# CHIP_dispv2_0.net
KiCad netlist of a schematic drawn in EAGLE
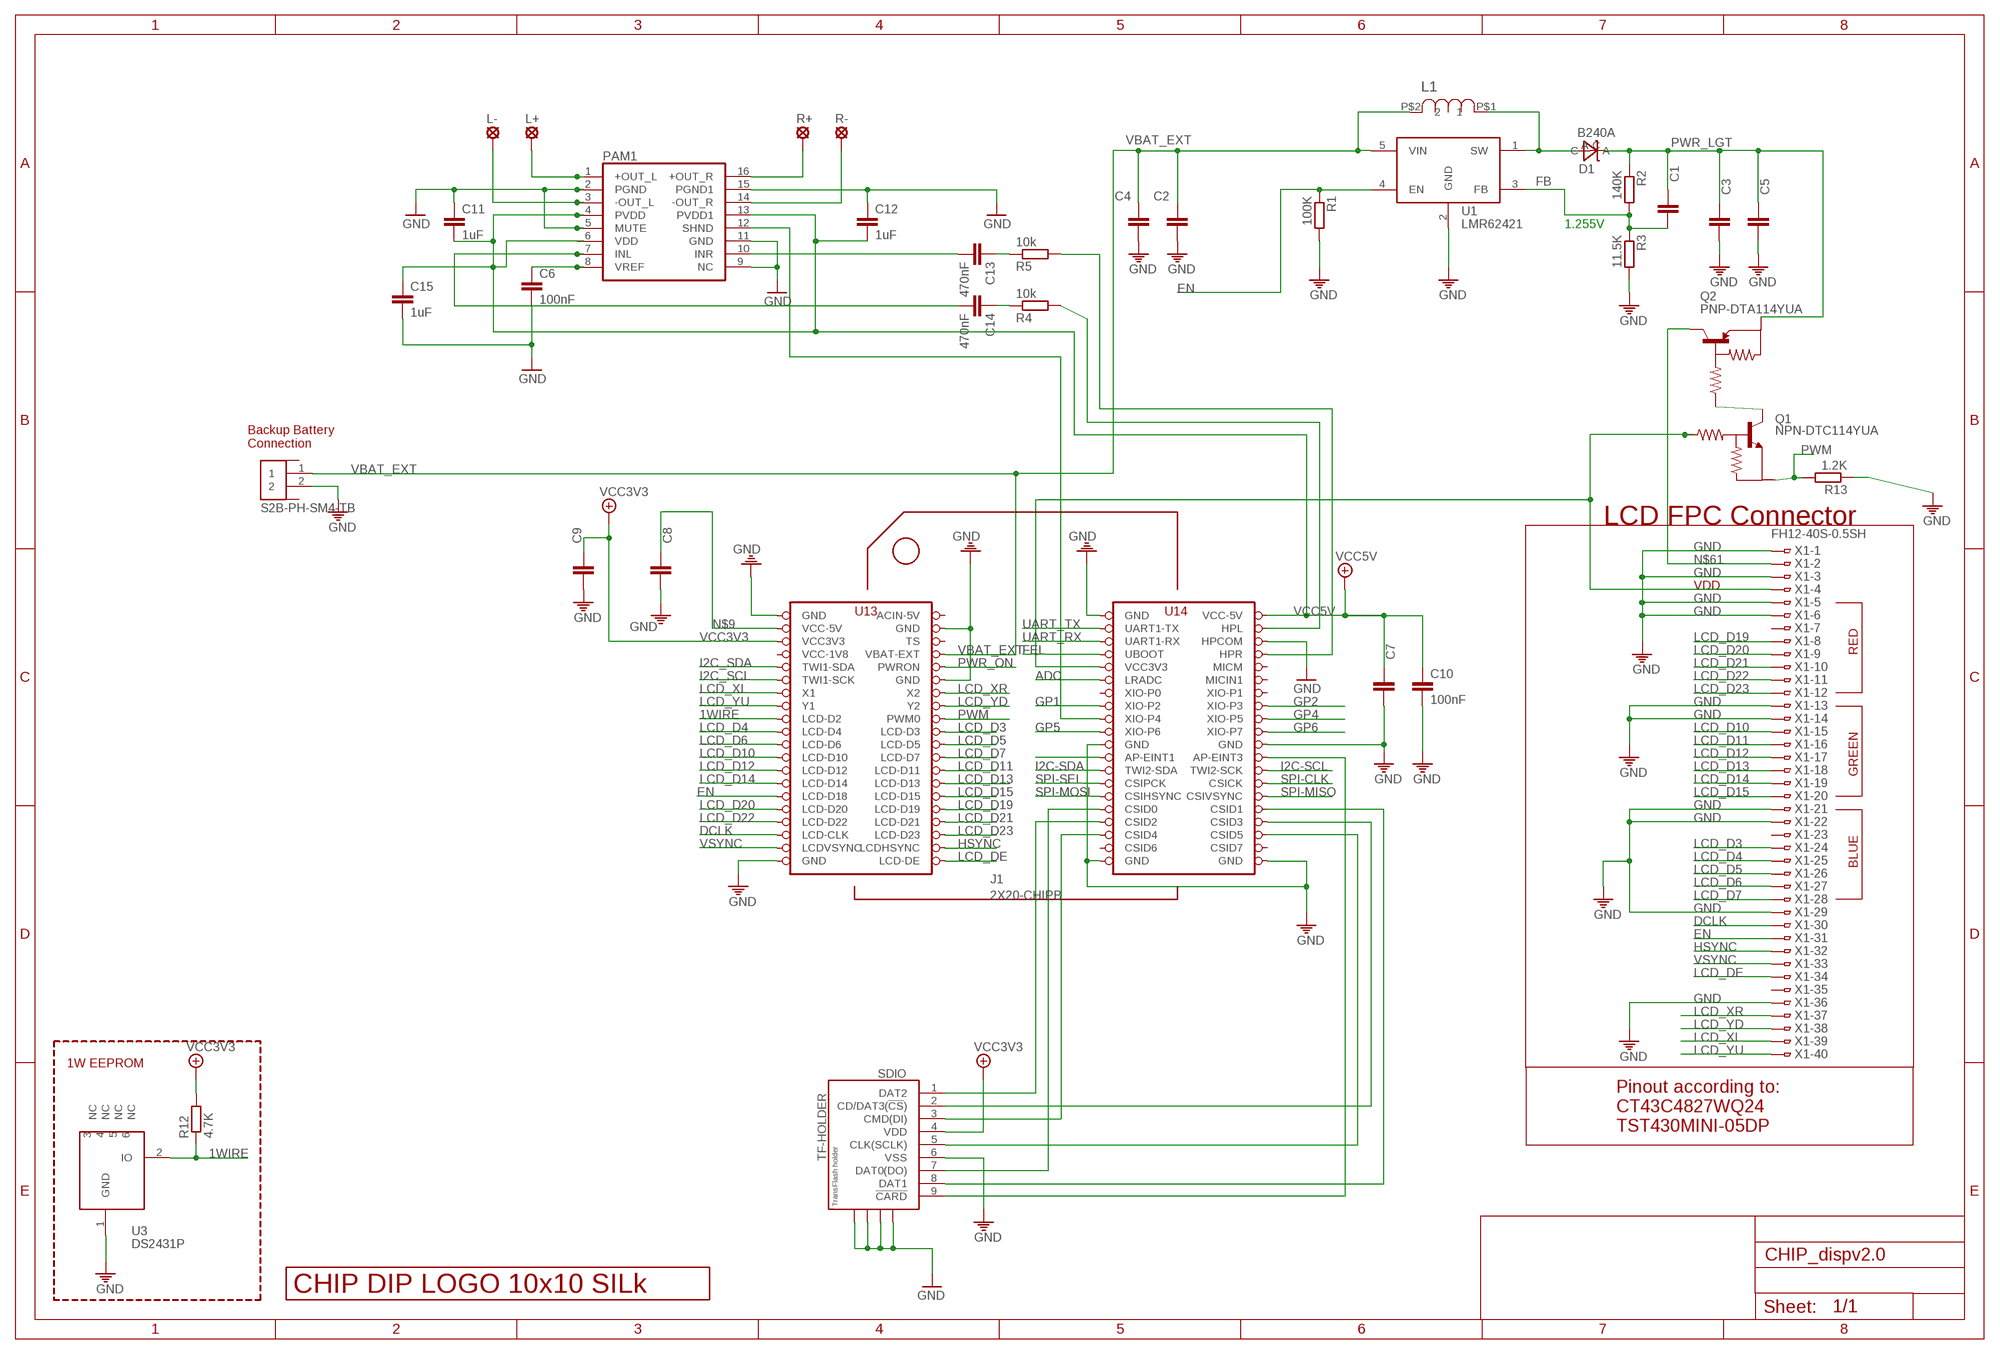
[diagram p0: schematic, sheet 1]

(export (version "E")
  (design (tool "Eeschema 10.0.6"))
  (components
    (comp (ref "C1")
      (value "220pF")
      (footprint "eagle-import:C0805")
      (libsource (lib "eagle-import") (part "C-EUC0805"))
    )
    (comp (ref "C2")
      (value "100nF")
      (footprint "eagle-import:C0805")
      (libsource (lib "eagle-import") (part "C-EUC0805"))
    )
    (comp (ref "C3")
      (value "100nF")
      (footprint "eagle-import:C0805")
      (libsource (lib "eagle-import") (part "C-EUC0805"))
    )
    (comp (ref "C4")
      (value "22uF")
      (footprint "eagle-import:C0805")
      (libsource (lib "eagle-import") (part "C-EUC0805"))
    )
    (comp (ref "C5")
      (value "22uF")
      (footprint "eagle-import:C0805")
      (libsource (lib "eagle-import") (part "C-EUC0805"))
    )
    (comp (ref "C6")
      (value "100nF")
      (footprint "eagle-import:C0805")
      (libsource (lib "eagle-import") (part "C-EUC0805"))
    )
    (comp (ref "C7")
      (value "22uF")
      (footprint "eagle-import:C0805")
      (libsource (lib "eagle-import") (part "C-EUC0805"))
    )
    (comp (ref "C8")
      (value "100nF")
      (footprint "eagle-import:C0805")
      (libsource (lib "eagle-import") (part "C-EUC0805"))
    )
    (comp (ref "C9")
      (value "100nF")
      (footprint "eagle-import:C0805")
      (libsource (lib "eagle-import") (part "C-EUC0805"))
    )
    (comp (ref "C10")
      (value "100nF")
      (footprint "eagle-import:C0805")
      (libsource (lib "eagle-import") (part "C-EUC0805"))
    )
    (comp (ref "C11")
      (value "1uF")
      (footprint "eagle-import:C0805")
      (libsource (lib "eagle-import") (part "C-EUC0805"))
    )
    (comp (ref "C12")
      (value "1uF")
      (footprint "eagle-import:C0805")
      (libsource (lib "eagle-import") (part "C-EUC0805"))
    )
    (comp (ref "C13")
      (value "470nF")
      (footprint "eagle-import:C0805")
      (libsource (lib "eagle-import") (part "C-EUC0805"))
    )
    (comp (ref "C14")
      (value "470nF")
      (footprint "eagle-import:C0805")
      (libsource (lib "eagle-import") (part "C-EUC0805"))
    )
    (comp (ref "C15")
      (value "1uF")
      (footprint "eagle-import:C0805")
      (libsource (lib "eagle-import") (part "C-EUC0805"))
    )
    (comp (ref "D1")
      (value "B240A")
      (footprint "eagle-import:DO-214AC")
      (fields (field (name "MFG") "DIGIKEY") (field (name "VENDOR_PART_NUMBER") "B240A-13-F"))
      (libsource (lib "eagle-import") (part "DIODE_SCHTKY_B240"))
    )
    (comp (ref "J1")
      (value "2X20-CHIPB")
      (footprint "eagle-import:2X20CHIP_SM")
      (libsource (lib "eagle-import") (part "2X20-CHIPB"))
    )
    (comp (ref "J3")
      (value "S2B-PH-SM4-TB")
      (footprint "eagle-import:S2B-PH-SM4-TB")
      (fields (field (name "MFG") "DIGIKEY") (field (name "VENDOR_PART_NUMBER") "S2B-PH-SM4-TB(LF)(SN)"))
      (libsource (lib "eagle-import") (part "S2B-PH-SM4-TB"))
    )
    (comp (ref "L+")
      (value "SE11")
      (footprint "eagle-import:SE11")
      (libsource (lib "eagle-import") (part "SE11"))
    )
    (comp (ref "L-")
      (value "SE11")
      (footprint "eagle-import:SE11")
      (libsource (lib "eagle-import") (part "SE11"))
    )
    (comp (ref "L1")
      (value "SRN6045-100M")
      (footprint "eagle-import:SRN6045")
      (fields (field (name "MFG") "DIGIKEY"))
      (libsource (lib "eagle-import") (part "SRN6045-100M"))
    )
    (comp (ref "PAM1")
      (value "PAM8403")
      (footprint "eagle-import:SOP-16")
      (libsource (lib "eagle-import") (part "PAM8403"))
    )
    (comp (ref "Q1")
      (value "NPN-DTC114YUA")
      (footprint "eagle-import:SOT323")
      (libsource (lib "eagle-import") (part "NPN-DTC114YUA"))
    )
    (comp (ref "Q2")
      (value "PNP-DTA114YUA")
      (footprint "eagle-import:SOT323")
      (libsource (lib "eagle-import") (part "PNP-DTA114YUA"))
    )
    (comp (ref "R+")
      (value "SE11")
      (footprint "eagle-import:SE11")
      (libsource (lib "eagle-import") (part "SE11"))
    )
    (comp (ref "R-")
      (value "SE11")
      (footprint "eagle-import:SE11")
      (libsource (lib "eagle-import") (part "SE11"))
    )
    (comp (ref "R1")
      (value "100K")
      (footprint "eagle-import:M0805")
      (libsource (lib "eagle-import") (part "R-EU_M0805"))
    )
    (comp (ref "R2")
      (value "140K")
      (footprint "eagle-import:M0805")
      (libsource (lib "eagle-import") (part "R-EU_M0805"))
    )
    (comp (ref "R3")
      (value "11.5K")
      (footprint "eagle-import:M0805")
      (libsource (lib "eagle-import") (part "R-EU_M0805"))
    )
    (comp (ref "R4")
      (value "10k")
      (footprint "eagle-import:R0805")
      (libsource (lib "eagle-import") (part "R-EU_R0805"))
    )
    (comp (ref "R5")
      (value "10k")
      (footprint "eagle-import:R0805")
      (libsource (lib "eagle-import") (part "R-EU_R0805"))
    )
    (comp (ref "R12")
      (value "4.7K")
      (footprint "eagle-import:M0805")
      (libsource (lib "eagle-import") (part "R-EU_M0805"))
    )
    (comp (ref "R13")
      (value "1.2K")
      (footprint "eagle-import:M0805")
      (libsource (lib "eagle-import") (part "R-EU_M0805"))
    )
    (comp (ref "SDIO")
      (value "TF-HOLDER")
      (footprint "eagle-import:TF-PULL")
      (libsource (lib "eagle-import") (part "TF-HOLDER"))
    )
    (comp (ref "U$2")
      (value "LOGO_10X10_SILK")
      (footprint "eagle-import:LOGO2_10X10_SILK")
      (libsource (lib "eagle-import") (part "LOGO_10X10_SILK"))
    )
    (comp (ref "U1")
      (value "LMR62421")
      (footprint "eagle-import:SOT23-5")
      (fields (field (name "MFG") "DIGIKEY") (field (name "VENDOR_PART_NUMBER") "LMR62421XMFE/NOPB"))
      (libsource (lib "eagle-import") (part "LMR62421"))
    )
    (comp (ref "U3")
      (value "DS2431P")
      (footprint "eagle-import:TSOC6")
      (fields (field (name "MFG") "DIGIKEY") (field (name "VENDOR_PART_NUMBER") "DS2431P+T&R"))
      (libsource (lib "eagle-import") (part "DS2431P"))
    )
    (comp (ref "X1")
      (value "FH12-40S-0.5SH")
      (footprint "eagle-import:FH12-40S-0.5SH")
      (fields (field (name "MFG") "DIGIKEY") (field (name "VENDOR_PART_NUMBER") "FH12-40S-0.5SH(55)"))
      (libsource (lib "eagle-import") (part "FH12-40S-0.5SH"))
    )
  )
  (nets
    (net (code "1") (name "/1WIRE") (class "Default")
      (node (ref "J1") (pin "LCD-D2") (pinfunction "LCD-D2_LCD-D2") (pintype "passive"))
      (node (ref "R12") (pin "1") (pinfunction "1_1") (pintype "passive"))
      (node (ref "U3") (pin "2") (pinfunction "IO_2") (pintype "bidirectional"))
    )
    (net (code "2") (name "/ADC") (class "Default")
      (node (ref "J1") (pin "LRADC") (pinfunction "LRADC_LRADC") (pintype "passive"))
    )
    (net (code "3") (name "/DCLK") (class "Default")
      (node (ref "J1") (pin "LCD-CLK") (pinfunction "LCD-CLK_LCD-CLK") (pintype "passive"))
      (node (ref "X1") (pin "30") (pinfunction "1_30") (pintype "passive"))
    )
    (net (code "4") (name "/EN") (class "Default")
      (node (ref "J1") (pin "LCD-D18") (pinfunction "LCD-D18_LCD-D18") (pintype "passive"))
      (node (ref "R1") (pin "1") (pinfunction "1_1") (pintype "passive"))
      (node (ref "U1") (pin "4") (pinfunction "EN_4") (pintype "bidirectional"))
      (node (ref "X1") (pin "31") (pinfunction "1_31") (pintype "passive"))
    )
    (net (code "5") (name "/FB") (class "Default")
      (node (ref "C1") (pin "2") (pinfunction "2_2") (pintype "passive"))
      (node (ref "R2") (pin "2") (pinfunction "2_2") (pintype "passive"))
      (node (ref "R3") (pin "1") (pinfunction "1_1") (pintype "passive"))
      (node (ref "U1") (pin "3") (pinfunction "FB_3") (pintype "bidirectional"))
    )
    (net (code "6") (name "/FEL") (class "Default")
      (node (ref "J1") (pin "FEL") (pinfunction "UBOOT_FEL") (pintype "passive"))
    )
    (net (code "7") (name "/GP1") (class "Default")
      (node (ref "J1") (pin "XIO-P2") (pinfunction "XIO-P2_XIO-P2") (pintype "passive"))
    )
    (net (code "8") (name "/GP2") (class "Default")
      (node (ref "J1") (pin "XIO-P3") (pinfunction "XIO-P3_XIO-P3") (pintype "passive"))
    )
    (net (code "9") (name "/GP4") (class "Default")
      (node (ref "J1") (pin "XIO-P5") (pinfunction "XIO-P5_XIO-P5") (pintype "passive"))
    )
    (net (code "10") (name "/GP5") (class "Default")
      (node (ref "J1") (pin "XIO-P6") (pinfunction "XIO-P6_XIO-P6") (pintype "passive"))
    )
    (net (code "11") (name "/GP6") (class "Default")
      (node (ref "J1") (pin "XIO-P7") (pinfunction "XIO-P7_XIO-P7") (pintype "passive"))
    )
    (net (code "12") (name "/HSYNC") (class "Default")
      (node (ref "J1") (pin "LCD-HSYNC") (pinfunction "LCDHSYNC_LCD-HSYNC") (pintype "passive"))
      (node (ref "X1") (pin "32") (pinfunction "1_32") (pintype "passive"))
    )
    (net (code "13") (name "/I2C-SCL") (class "Default")
      (node (ref "J1") (pin "TWI2-SCK") (pinfunction "TWI2-SCK_TWI2-SCK") (pintype "passive"))
    )
    (net (code "14") (name "/I2C-SDA") (class "Default")
      (node (ref "J1") (pin "TWI2-SDA") (pinfunction "TWI2-SDA_TWI2-SDA") (pintype "passive"))
    )
    (net (code "15") (name "/I2C_SCL") (class "Default")
      (node (ref "J1") (pin "TWI1-SCK") (pinfunction "TWI1-SCK_TWI1-SCK") (pintype "passive"))
    )
    (net (code "16") (name "/I2C_SDA") (class "Default")
      (node (ref "J1") (pin "TWI1-SDA") (pinfunction "TWI1-SDA_TWI1-SDA") (pintype "passive"))
    )
    (net (code "17") (name "/LCD_D3") (class "Default")
      (node (ref "J1") (pin "LCD-D3") (pinfunction "LCD-D3_LCD-D3") (pintype "passive"))
      (node (ref "X1") (pin "24") (pinfunction "1_24") (pintype "passive"))
    )
    (net (code "18") (name "/LCD_D4") (class "Default")
      (node (ref "J1") (pin "LCD-D4") (pinfunction "LCD-D4_LCD-D4") (pintype "passive"))
      (node (ref "X1") (pin "25") (pinfunction "1_25") (pintype "passive"))
    )
    (net (code "19") (name "/LCD_D5") (class "Default")
      (node (ref "J1") (pin "LCD-D5") (pinfunction "LCD-D5_LCD-D5") (pintype "passive"))
      (node (ref "X1") (pin "26") (pinfunction "1_26") (pintype "passive"))
    )
    (net (code "20") (name "/LCD_D6") (class "Default")
      (node (ref "J1") (pin "LCD-D6") (pinfunction "LCD-D6_LCD-D6") (pintype "passive"))
      (node (ref "X1") (pin "27") (pinfunction "1_27") (pintype "passive"))
    )
    (net (code "21") (name "/LCD_D7") (class "Default")
      (node (ref "J1") (pin "LCD-D7") (pinfunction "LCD-D7_LCD-D7") (pintype "passive"))
      (node (ref "X1") (pin "28") (pinfunction "1_28") (pintype "passive"))
    )
    (net (code "22") (name "/LCD_D10") (class "Default")
      (node (ref "J1") (pin "LCD-D10") (pinfunction "LCD-D10_LCD-D10") (pintype "passive"))
      (node (ref "X1") (pin "15") (pinfunction "1_15") (pintype "passive"))
    )
    (net (code "23") (name "/LCD_D11") (class "Default")
      (node (ref "J1") (pin "LCD-D11") (pinfunction "LCD-D11_LCD-D11") (pintype "passive"))
      (node (ref "X1") (pin "16") (pinfunction "1_16") (pintype "passive"))
    )
    (net (code "24") (name "/LCD_D12") (class "Default")
      (node (ref "J1") (pin "LCD-D12") (pinfunction "LCD-D12_LCD-D12") (pintype "passive"))
      (node (ref "X1") (pin "17") (pinfunction "1_17") (pintype "passive"))
    )
    (net (code "25") (name "/LCD_D13") (class "Default")
      (node (ref "J1") (pin "LCD-D13") (pinfunction "LCD-D13_LCD-D13") (pintype "passive"))
      (node (ref "X1") (pin "18") (pinfunction "1_18") (pintype "passive"))
    )
    (net (code "26") (name "/LCD_D14") (class "Default")
      (node (ref "J1") (pin "LCD-D14") (pinfunction "LCD-D14_LCD-D14") (pintype "passive"))
      (node (ref "X1") (pin "19") (pinfunction "1_19") (pintype "passive"))
    )
    (net (code "27") (name "/LCD_D15") (class "Default")
      (node (ref "J1") (pin "LCD-D15") (pinfunction "LCD-D15_LCD-D15") (pintype "passive"))
      (node (ref "X1") (pin "20") (pinfunction "1_20") (pintype "passive"))
    )
    (net (code "28") (name "/LCD_D19") (class "Default")
      (node (ref "J1") (pin "LCD-D19") (pinfunction "LCD-D19_LCD-D19") (pintype "passive"))
      (node (ref "X1") (pin "8") (pinfunction "1_8") (pintype "passive"))
    )
    (net (code "29") (name "/LCD_D20") (class "Default")
      (node (ref "J1") (pin "LCD-D20") (pinfunction "LCD-D20_LCD-D20") (pintype "passive"))
      (node (ref "X1") (pin "9") (pinfunction "1_9") (pintype "passive"))
    )
    (net (code "30") (name "/LCD_D21") (class "Default")
      (node (ref "J1") (pin "LCD-D21") (pinfunction "LCD-D21_LCD-D21") (pintype "passive"))
      (node (ref "X1") (pin "10") (pinfunction "1_10") (pintype "passive"))
    )
    (net (code "31") (name "/LCD_D22") (class "Default")
      (node (ref "J1") (pin "LCD-D22") (pinfunction "LCD-D22_LCD-D22") (pintype "passive"))
      (node (ref "X1") (pin "11") (pinfunction "1_11") (pintype "passive"))
    )
    (net (code "32") (name "/LCD_D23") (class "Default")
      (node (ref "J1") (pin "LCD-D23") (pinfunction "LCD-D23_LCD-D23") (pintype "passive"))
      (node (ref "X1") (pin "12") (pinfunction "1_12") (pintype "passive"))
    )
    (net (code "33") (name "/LCD_DE") (class "Default")
      (node (ref "J1") (pin "LCD-DE") (pinfunction "LCD-DE_LCD-DE") (pintype "passive"))
      (node (ref "X1") (pin "34") (pinfunction "1_34") (pintype "passive"))
    )
    (net (code "34") (name "/LCD_XL") (class "Default")
      (node (ref "J1") (pin "X1") (pinfunction "X1_X1") (pintype "passive"))
      (node (ref "X1") (pin "39") (pinfunction "1_39") (pintype "passive"))
    )
    (net (code "35") (name "/LCD_XR") (class "Default")
      (node (ref "J1") (pin "X2") (pinfunction "X2_X2") (pintype "passive"))
      (node (ref "X1") (pin "37") (pinfunction "1_37") (pintype "passive"))
    )
    (net (code "36") (name "/LCD_YD") (class "Default")
      (node (ref "J1") (pin "Y2") (pinfunction "Y2_Y2") (pintype "passive"))
      (node (ref "X1") (pin "38") (pinfunction "1_38") (pintype "passive"))
    )
    (net (code "37") (name "/LCD_YU") (class "Default")
      (node (ref "J1") (pin "Y1") (pinfunction "Y1_Y1") (pintype "passive"))
      (node (ref "X1") (pin "40") (pinfunction "1_40") (pintype "passive"))
    )
    (net (code "38") (name "/N$9") (class "Default")
      (node (ref "C8") (pin "1") (pinfunction "1_1") (pintype "passive"))
      (node (ref "J1") (pin "VCC5V@0") (pinfunction "VCC-5V_VCC5V@0") (pintype "power_in"))
    )
    (net (code "39") (name "/N$61") (class "Default")
      (node (ref "Q2") (pin "3") (pinfunction "OUT_3") (pintype "passive"))
      (node (ref "X1") (pin "2") (pinfunction "1_2") (pintype "passive"))
    )
    (net (code "40") (name "/PWM") (class "Default")
      (node (ref "J1") (pin "PWM0") (pinfunction "PWM0_PWM0") (pintype "passive"))
      (node (ref "Q1") (pin "2") (pinfunction "GND_2") (pintype "passive"))
      (node (ref "R13") (pin "2") (pinfunction "2_2") (pintype "passive"))
    )
    (net (code "41") (name "/PWR_LGT") (class "Default")
      (node (ref "C1") (pin "1") (pinfunction "1_1") (pintype "passive"))
      (node (ref "C3") (pin "1") (pinfunction "1_1") (pintype "passive"))
      (node (ref "C5") (pin "1") (pinfunction "1_1") (pintype "passive"))
      (node (ref "D1") (pin "C") (pinfunction "C_C") (pintype "bidirectional"))
      (node (ref "Q2") (pin "2") (pinfunction "GND_2") (pintype "passive"))
      (node (ref "R2") (pin "1") (pinfunction "1_1") (pintype "passive"))
    )
    (net (code "42") (name "/PWR_ON") (class "Default")
      (node (ref "J1") (pin "PWRON") (pinfunction "PWRON_PWRON") (pintype "passive"))
    )
    (net (code "43") (name "/SPI-CLK") (class "Default")
      (node (ref "J1") (pin "CSICK") (pinfunction "CSICK_CSICK") (pintype "passive"))
    )
    (net (code "44") (name "/SPI-MISO") (class "Default")
      (node (ref "J1") (pin "CSIVSYNC") (pinfunction "CSIVSYNC_CSIVSYNC") (pintype "passive"))
    )
    (net (code "45") (name "/SPI-MOSI") (class "Default")
      (node (ref "J1") (pin "CSIHSYNC") (pinfunction "CSIHSYNC_CSIHSYNC") (pintype "passive"))
    )
    (net (code "46") (name "/SPI-SEL") (class "Default")
      (node (ref "J1") (pin "CSIPCK") (pinfunction "CSIPCK_CSIPCK") (pintype "passive"))
    )
    (net (code "47") (name "/UART_RX") (class "Default")
      (node (ref "J1") (pin "UART1-RX") (pinfunction "UART1-RX_UART1-RX") (pintype "passive"))
    )
    (net (code "48") (name "/UART_TX") (class "Default")
      (node (ref "J1") (pin "UART1-TX") (pinfunction "UART1-TX_UART1-TX") (pintype "passive"))
    )
    (net (code "49") (name "/VBAT_EXT") (class "Default")
      (node (ref "C2") (pin "1") (pinfunction "1_1") (pintype "passive"))
      (node (ref "C4") (pin "1") (pinfunction "1_1") (pintype "passive"))
      (node (ref "J1") (pin "BAT") (pinfunction "VBAT-EXT_BAT") (pintype "passive"))
      (node (ref "J3") (pin "1") (pinfunction "1_1") (pintype "bidirectional"))
      (node (ref "L1") (pin "P$2") (pinfunction "2_P$2") (pintype "passive"))
      (node (ref "U1") (pin "5") (pinfunction "VIN_5") (pintype "bidirectional"))
    )
    (net (code "50") (name "/VCC-1V8") (class "Default")
      (node (ref "J1") (pin "VCC1V8") (pinfunction "VCC-1V8_VCC1V8") (pintype "power_in"))
    )
    (net (code "51") (name "/VSYNC") (class "Default")
      (node (ref "J1") (pin "LCD-VSYNC") (pinfunction "LCDVSYNC_LCD-VSYNC") (pintype "passive"))
      (node (ref "X1") (pin "33") (pinfunction "1_33") (pintype "passive"))
    )
    (net (code "52") (name "GND") (class "Default")
      (node (ref "C10") (pin "2") (pinfunction "2_2") (pintype "passive"))
      (node (ref "C11") (pin "1") (pinfunction "1_1") (pintype "passive"))
      (node (ref "C12") (pin "1") (pinfunction "1_1") (pintype "passive"))
      (node (ref "C15") (pin "2") (pinfunction "2_2") (pintype "passive"))
      (node (ref "C2") (pin "2") (pinfunction "2_2") (pintype "passive"))
      (node (ref "C3") (pin "2") (pinfunction "2_2") (pintype "passive"))
      (node (ref "C4") (pin "2") (pinfunction "2_2") (pintype "passive"))
      (node (ref "C5") (pin "2") (pinfunction "2_2") (pintype "passive"))
      (node (ref "C6") (pin "2") (pinfunction "2_2") (pintype "passive"))
      (node (ref "C7") (pin "2") (pinfunction "2_2") (pintype "passive"))
      (node (ref "C8") (pin "2") (pinfunction "2_2") (pintype "passive"))
      (node (ref "C9") (pin "2") (pinfunction "2_2") (pintype "passive"))
      (node (ref "J1") (pin "GND@1") (pinfunction "GND_GND@1") (pintype "power_in"))
      (node (ref "J1") (pin "GND@10") (pinfunction "GND_GND@10") (pintype "power_in"))
      (node (ref "J1") (pin "GND@2") (pinfunction "GND_GND@2") (pintype "power_in"))
      (node (ref "J1") (pin "GND@3") (pinfunction "GND_GND@3") (pintype "power_in"))
      (node (ref "J1") (pin "GND@4") (pinfunction "GND_GND@4") (pintype "power_in"))
      (node (ref "J1") (pin "GND@5") (pinfunction "GND_GND@5") (pintype "power_in"))
      (node (ref "J1") (pin "GND@6") (pinfunction "GND_GND@6") (pintype "power_in"))
      (node (ref "J1") (pin "GND@7") (pinfunction "GND_GND@7") (pintype "power_in"))
      (node (ref "J1") (pin "GND@8") (pinfunction "GND_GND@8") (pintype "power_in"))
      (node (ref "J1") (pin "HPCOM") (pinfunction "HPCOM_HPCOM") (pintype "passive"))
      (node (ref "J3") (pin "2") (pinfunction "2_2") (pintype "bidirectional"))
      (node (ref "PAM1") (pin "11") (pinfunction "GND_11") (pintype "output"))
      (node (ref "PAM1") (pin "15") (pinfunction "PGND1_15") (pintype "output"))
      (node (ref "PAM1") (pin "2") (pinfunction "PGND_2") (pintype "input"))
      (node (ref "PAM1") (pin "5") (pinfunction "MUTE_5") (pintype "input"))
      (node (ref "PAM1") (pin "9") (pinfunction "NC_9") (pintype "output"))
      (node (ref "R1") (pin "2") (pinfunction "2_2") (pintype "passive"))
      (node (ref "R13") (pin "1") (pinfunction "1_1") (pintype "passive"))
      (node (ref "R3") (pin "2") (pinfunction "2_2") (pintype "passive"))
      (node (ref "SDIO") (pin "6") (pinfunction "VSS_6") (pintype "power_in"))
      (node (ref "SDIO") (pin "S1") (pinfunction "S1_S1") (pintype "passive"))
      (node (ref "SDIO") (pin "S2") (pinfunction "S2_S2") (pintype "passive"))
      (node (ref "SDIO") (pin "S3") (pinfunction "S3_S3") (pintype "passive"))
      (node (ref "SDIO") (pin "S4") (pinfunction "S4_S4") (pintype "passive"))
      (node (ref "U1") (pin "2") (pinfunction "GND_2") (pintype "bidirectional"))
      (node (ref "U3") (pin "1") (pinfunction "GND_1") (pintype "bidirectional"))
      (node (ref "X1") (pin "1") (pinfunction "1_1") (pintype "passive"))
      (node (ref "X1") (pin "13") (pinfunction "1_13") (pintype "passive"))
      (node (ref "X1") (pin "14") (pinfunction "1_14") (pintype "passive"))
      (node (ref "X1") (pin "21") (pinfunction "1_21") (pintype "passive"))
      (node (ref "X1") (pin "22") (pinfunction "1_22") (pintype "passive"))
      (node (ref "X1") (pin "29") (pinfunction "1_29") (pintype "passive"))
      (node (ref "X1") (pin "3") (pinfunction "1_3") (pintype "passive"))
      (node (ref "X1") (pin "36") (pinfunction "1_36") (pintype "passive"))
      (node (ref "X1") (pin "5") (pinfunction "1_5") (pintype "passive"))
      (node (ref "X1") (pin "6") (pinfunction "1_6") (pintype "passive"))
    )
    (net (code "53") (name "Net-(C13-Pad1)") (class "Default")
      (node (ref "C13") (pin "1") (pinfunction "1_1") (pintype "passive"))
      (node (ref "R5") (pin "1") (pinfunction "1_1") (pintype "passive"))
    )
    (net (code "54") (name "Net-(C14-Pad1)") (class "Default")
      (node (ref "C14") (pin "1") (pinfunction "1_1") (pintype "passive"))
      (node (ref "R4") (pin "1") (pinfunction "1_1") (pintype "passive"))
    )
    (net (code "55") (name "Net-(J1-PadHPL)") (class "Default")
      (node (ref "J1") (pin "HPL") (pinfunction "HPL_HPL") (pintype "passive"))
      (node (ref "R4") (pin "2") (pinfunction "2_2") (pintype "passive"))
    )
    (net (code "56") (name "Net-(J1-PadHPR)") (class "Default")
      (node (ref "J1") (pin "HPR") (pinfunction "HPR_HPR") (pintype "passive"))
      (node (ref "R5") (pin "2") (pinfunction "2_2") (pintype "passive"))
    )
    (net (code "57") (name "Net-(L1-1)") (class "Default")
      (node (ref "D1") (pin "A") (pinfunction "A_A") (pintype "bidirectional"))
      (node (ref "L1") (pin "P$1") (pinfunction "1_P$1") (pintype "passive"))
      (node (ref "U1") (pin "1") (pinfunction "SW_1") (pintype "bidirectional"))
    )
    (net (code "58") (name "Net-(PAM1-+OUT_L)") (class "Default")
      (node (ref "L+") (pin "MP") (pinfunction "MP_MP") (pintype "passive"))
      (node (ref "PAM1") (pin "1") (pinfunction "+OUT_L_1") (pintype "input"))
    )
    (net (code "59") (name "Net-(PAM1-+OUT_R)") (class "Default")
      (node (ref "PAM1") (pin "16") (pinfunction "+OUT_R_16") (pintype "output"))
      (node (ref "R+") (pin "MP") (pinfunction "MP_MP") (pintype "passive"))
    )
    (net (code "60") (name "Net-(PAM1--OUT_L)") (class "Default")
      (node (ref "L-") (pin "MP") (pinfunction "MP_MP") (pintype "passive"))
      (node (ref "PAM1") (pin "3") (pinfunction "-OUT_L_3") (pintype "input"))
    )
    (net (code "61") (name "Net-(PAM1--OUT_R)") (class "Default")
      (node (ref "PAM1") (pin "14") (pinfunction "-OUT_R_14") (pintype "output"))
      (node (ref "R-") (pin "MP") (pinfunction "MP_MP") (pintype "passive"))
    )
    (net (code "62") (name "Net-(PAM1-INL)") (class "Default")
      (node (ref "C14") (pin "2") (pinfunction "2_2") (pintype "passive"))
      (node (ref "PAM1") (pin "7") (pinfunction "INL_7") (pintype "input"))
    )
    (net (code "63") (name "Net-(PAM1-INR)") (class "Default")
      (node (ref "C13") (pin "2") (pinfunction "2_2") (pintype "passive"))
      (node (ref "PAM1") (pin "10") (pinfunction "INR_10") (pintype "output"))
    )
    (net (code "64") (name "Net-(PAM1-SHND)") (class "Default")
      (node (ref "J1") (pin "XIO-P4") (pinfunction "XIO-P4_XIO-P4") (pintype "passive"))
      (node (ref "PAM1") (pin "12") (pinfunction "SHND_12") (pintype "output"))
    )
    (net (code "65") (name "Net-(PAM1-VREF)") (class "Default")
      (node (ref "C6") (pin "1") (pinfunction "1_1") (pintype "passive"))
      (node (ref "PAM1") (pin "8") (pinfunction "VREF_8") (pintype "input"))
    )
    (net (code "66") (name "Net-(Q1-IN)") (class "Default")
      (node (ref "J1") (pin "VCC3V3@1") (pinfunction "VCC3V3_VCC3V3@1") (pintype "power_in"))
      (node (ref "Q1") (pin "1") (pinfunction "IN_1") (pintype "passive"))
      (node (ref "X1") (pin "4") (pinfunction "1_4") (pintype "passive"))
    )
    (net (code "67") (name "Net-(Q1-OUT)") (class "Default")
      (node (ref "Q1") (pin "3") (pinfunction "OUT_3") (pintype "passive"))
      (node (ref "Q2") (pin "1") (pinfunction "IN_1") (pintype "passive"))
    )
    (net (code "68") (name "Net-(SDIO-CD{slash}DAT3(~{CS}))") (class "Default")
      (node (ref "J1") (pin "CSID3") (pinfunction "CSID3_CSID3") (pintype "passive"))
      (node (ref "SDIO") (pin "2") (pinfunction "CD/DAT3(~{CS})_2") (pintype "bidirectional"))
    )
    (net (code "69") (name "Net-(SDIO-CLK(SCLK))") (class "Default")
      (node (ref "J1") (pin "CSID5") (pinfunction "CSID5_CSID5") (pintype "passive"))
      (node (ref "SDIO") (pin "5") (pinfunction "CLK(SCLK)_5") (pintype "input"))
    )
    (net (code "70") (name "Net-(SDIO-CMD(DI))") (class "Default")
      (node (ref "J1") (pin "CSID4") (pinfunction "CSID4_CSID4") (pintype "passive"))
      (node (ref "SDIO") (pin "3") (pinfunction "CMD(DI)_3") (pintype "bidirectional"))
    )
    (net (code "71") (name "Net-(SDIO-DAT0(DO))") (class "Default")
      (node (ref "J1") (pin "CSID0") (pinfunction "CSID0_CSID0") (pintype "passive"))
      (node (ref "SDIO") (pin "7") (pinfunction "DAT0(DO)_7") (pintype "bidirectional"))
    )
    (net (code "72") (name "Net-(SDIO-DAT1)") (class "Default")
      (node (ref "J1") (pin "CSID1") (pinfunction "CSID1_CSID1") (pintype "passive"))
      (node (ref "SDIO") (pin "8") (pinfunction "DAT1_8") (pintype "bidirectional"))
    )
    (net (code "73") (name "Net-(SDIO-DAT2)") (class "Default")
      (node (ref "J1") (pin "CSID2") (pinfunction "CSID2_CSID2") (pintype "passive"))
      (node (ref "SDIO") (pin "1") (pinfunction "DAT2_1") (pintype "bidirectional"))
    )
    (net (code "74") (name "Net-(SDIO-~{CARD})") (class "Default")
      (node (ref "J1") (pin "AP-EINT3") (pinfunction "AP-EINT3_AP-EINT3") (pintype "passive"))
      (node (ref "SDIO") (pin "9") (pinfunction "~{CARD}_9") (pintype "passive"))
    )
    (net (code "75") (name "VCC3V3") (class "Default")
      (node (ref "C9") (pin "1") (pinfunction "1_1") (pintype "passive"))
      (node (ref "J1") (pin "VCC3V3") (pinfunction "VCC3V3_VCC3V3") (pintype "power_in"))
      (node (ref "R12") (pin "2") (pinfunction "2_2") (pintype "passive"))
      (node (ref "SDIO") (pin "4") (pinfunction "VDD_4") (pintype "power_in"))
    )
    (net (code "76") (name "VCC5V") (class "Default")
      (node (ref "C10") (pin "1") (pinfunction "1_1") (pintype "passive"))
      (node (ref "C11") (pin "2") (pinfunction "2_2") (pintype "passive"))
      (node (ref "C12") (pin "2") (pinfunction "2_2") (pintype "passive"))
      (node (ref "C15") (pin "1") (pinfunction "1_1") (pintype "passive"))
      (node (ref "C7") (pin "1") (pinfunction "1_1") (pintype "passive"))
      (node (ref "J1") (pin "VCC5V@1") (pinfunction "VCC-5V_VCC5V@1") (pintype "power_in"))
      (node (ref "PAM1") (pin "13") (pinfunction "PVDD1_13") (pintype "output"))
      (node (ref "PAM1") (pin "4") (pinfunction "PVDD_4") (pintype "input"))
      (node (ref "PAM1") (pin "6") (pinfunction "VDD_6") (pintype "input"))
    )
    (net (code "77") (name "unconnected-(J1-ACIN-5V-PadCHG-IN)") (class "Default")
      (node (ref "J1") (pin "CHG-IN") (pinfunction "ACIN-5V_CHG-IN") (pintype "passive"))
    )
    (net (code "78") (name "unconnected-(J1-PadAP-EINT1)") (class "Default")
      (node (ref "J1") (pin "AP-EINT1") (pinfunction "AP-EINT1_AP-EINT1") (pintype "passive"))
    )
    (net (code "79") (name "unconnected-(J1-PadCSID6)") (class "Default")
      (node (ref "J1") (pin "CSID6") (pinfunction "CSID6_CSID6") (pintype "passive"))
    )
    (net (code "80") (name "unconnected-(J1-PadCSID7)") (class "Default")
      (node (ref "J1") (pin "CSID7") (pinfunction "CSID7_CSID7") (pintype "passive"))
    )
    (net (code "81") (name "unconnected-(J1-PadMICIN1)") (class "Default")
      (node (ref "J1") (pin "MICIN1") (pinfunction "MICIN1_MICIN1") (pintype "passive"))
    )
    (net (code "82") (name "unconnected-(J1-PadMICM)") (class "Default")
      (node (ref "J1") (pin "MICM") (pinfunction "MICM_MICM") (pintype "passive"))
    )
    (net (code "83") (name "unconnected-(J1-PadTS)") (class "Default")
      (node (ref "J1") (pin "TS") (pinfunction "TS_TS") (pintype "passive"))
    )
    (net (code "84") (name "unconnected-(J1-PadXIO-P0)") (class "Default")
      (node (ref "J1") (pin "XIO-P0") (pinfunction "XIO-P0_XIO-P0") (pintype "passive"))
    )
    (net (code "85") (name "unconnected-(J1-PadXIO-P1)") (class "Default")
      (node (ref "J1") (pin "XIO-P1") (pinfunction "XIO-P1_XIO-P1") (pintype "passive"))
    )
    (net (code "86") (name "unconnected-(J3-PadMNT1)") (class "Default")
      (node (ref "J3") (pin "MNT1") (pinfunction "MNT1_MNT1") (pintype "no_connect"))
    )
    (net (code "87") (name "unconnected-(J3-PadMNT2)") (class "Default")
      (node (ref "J3") (pin "MNT2") (pinfunction "MNT2_MNT2") (pintype "no_connect"))
    )
    (net (code "88") (name "unconnected-(U3-NC-Pad3)") (class "Default")
      (node (ref "U3") (pin "3") (pinfunction "NC_3") (pintype "bidirectional"))
    )
    (net (code "89") (name "unconnected-(U3-NC-Pad4)") (class "Default")
      (node (ref "U3") (pin "4") (pinfunction "NC_4") (pintype "bidirectional"))
    )
    (net (code "90") (name "unconnected-(U3-NC-Pad5)") (class "Default")
      (node (ref "U3") (pin "5") (pinfunction "NC_5") (pintype "bidirectional"))
    )
    (net (code "91") (name "unconnected-(U3-NC-Pad6)") (class "Default")
      (node (ref "U3") (pin "6") (pinfunction "NC_6") (pintype "bidirectional"))
    )
    (net (code "92") (name "unconnected-(X1AC-1-Pad35)") (class "Default")
      (node (ref "X1") (pin "35") (pinfunction "1_35") (pintype "passive"))
    )
    (net (code "93") (name "unconnected-(X1AL-1-Pad7)") (class "Default")
      (node (ref "X1") (pin "7") (pinfunction "1_7") (pintype "passive"))
    )
    (net (code "94") (name "unconnected-(X1P-1-Pad23)") (class "Default")
      (node (ref "X1") (pin "23") (pinfunction "1_23") (pintype "passive"))
    )
  )
)
